# brd-relays3.net
KiCad netlist of a schematic drawn in EAGLE
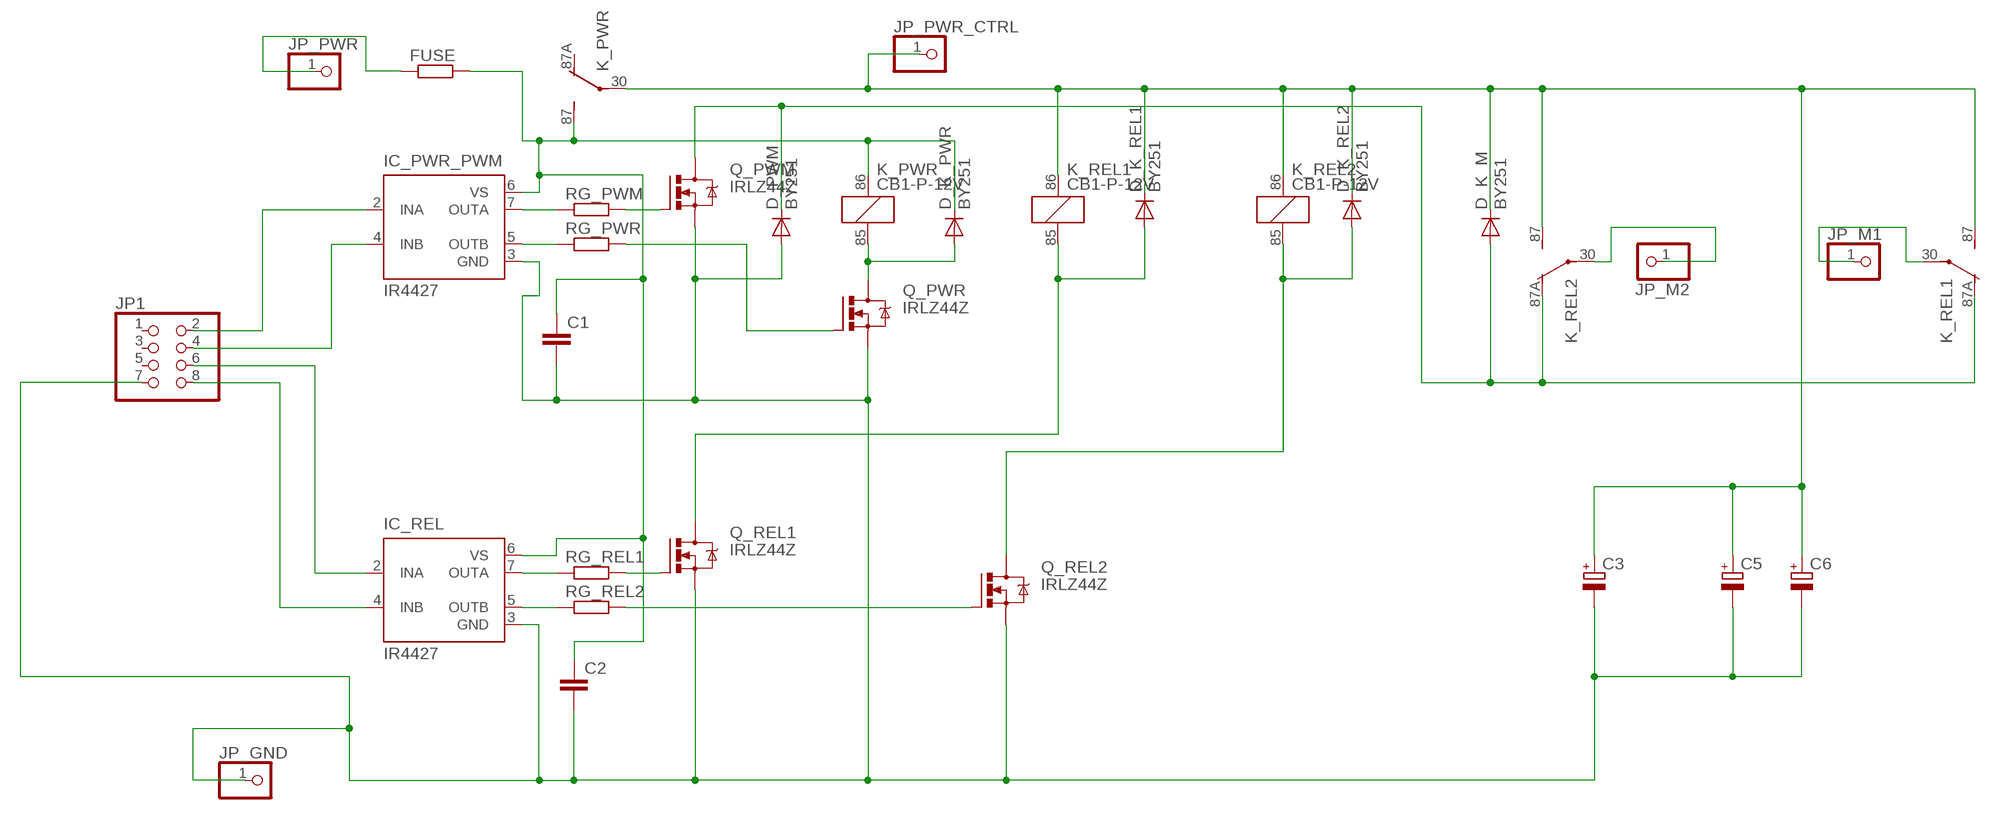
[diagram p0: schematic, sheet 1]

(export (version "E")
  (design (tool "Eeschema 10.0.6"))
  (components
    (comp (ref "C1")
      (value "C-EU050-055X075")
      (footprint "eagle-import:C050-055X075")
      (libsource (lib "eagle-import") (part "C-EU050-055X075"))
    )
    (comp (ref "C2")
      (value "C-EU050-055X075")
      (footprint "eagle-import:C050-055X075")
      (libsource (lib "eagle-import") (part "C-EU050-055X075"))
    )
    (comp (ref "C3")
      (value "CPOL-EUE5-13")
      (footprint "eagle-import:E5-13")
      (libsource (lib "eagle-import") (part "CPOL-EUE5-13"))
    )
    (comp (ref "C5")
      (value "CPOL-EUE5-13")
      (footprint "eagle-import:E5-13")
      (libsource (lib "eagle-import") (part "CPOL-EUE5-13"))
    )
    (comp (ref "C6")
      (value "CPOL-EUE5-13")
      (footprint "eagle-import:E5-13")
      (libsource (lib "eagle-import") (part "CPOL-EUE5-13"))
    )
    (comp (ref "D_K_M")
      (value "BY251")
      (footprint "eagle-import:DO201-15")
      (libsource (lib "eagle-import") (part "BY251"))
    )
    (comp (ref "D_K_PWR")
      (value "BY251")
      (footprint "eagle-import:DO201-15")
      (libsource (lib "eagle-import") (part "BY251"))
    )
    (comp (ref "D_K_REL1")
      (value "BY251")
      (footprint "eagle-import:DO201-15")
      (libsource (lib "eagle-import") (part "BY251"))
    )
    (comp (ref "D_K_REL2")
      (value "BY251")
      (footprint "eagle-import:DO201-15")
      (libsource (lib "eagle-import") (part "BY251"))
    )
    (comp (ref "D_PWM")
      (value "BY251")
      (footprint "eagle-import:DO201-15")
      (libsource (lib "eagle-import") (part "BY251"))
    )
    (comp (ref "FUSE")
      (value "R-EU_0207/10")
      (footprint "eagle-import:FUSE_PACK1")
      (libsource (lib "eagle-import") (part "R-EU_0207/10"))
    )
    (comp (ref "IC_PWR_PWM")
      (value "IR4427")
      (footprint "eagle-import:DIL08")
      (fields (field (name "MF") "INTERNATIONAL RECTIFIER(IR)"))
      (libsource (lib "eagle-import") (part "IR4427"))
    )
    (comp (ref "IC_REL")
      (value "IR4427")
      (footprint "eagle-import:DIL08")
      (fields (field (name "MF") "INTERNATIONAL RECTIFIER(IR)"))
      (libsource (lib "eagle-import") (part "IR4427"))
    )
    (comp (ref "JP1")
      (value "PINHD-2X4")
      (footprint "eagle-import:2X04")
      (libsource (lib "eagle-import") (part "PINHD-2X4"))
    )
    (comp (ref "JP_GND")
      (value "PINHD-1X1")
      (footprint "eagle-import:1X01")
      (libsource (lib "eagle-import") (part "PINHD-1X1"))
    )
    (comp (ref "JP_M1")
      (value "PINHD-1X1")
      (footprint "eagle-import:1X01")
      (libsource (lib "eagle-import") (part "PINHD-1X1"))
    )
    (comp (ref "JP_M2")
      (value "PINHD-1X1")
      (footprint "eagle-import:1X01")
      (libsource (lib "eagle-import") (part "PINHD-1X1"))
    )
    (comp (ref "JP_PWR")
      (value "PINHD-1X1")
      (footprint "eagle-import:1X01")
      (libsource (lib "eagle-import") (part "PINHD-1X1"))
    )
    (comp (ref "JP_PWR_CTRL")
      (value "PINHD-1X1")
      (footprint "eagle-import:1X01")
      (libsource (lib "eagle-import") (part "PINHD-1X1"))
    )
    (comp (ref "K_PWR")
      (value "CB1-P-12V")
      (footprint "eagle-import:CB1")
      (fields (field (name "MF") "AROMAT/ MATSUSHITA"))
      (libsource (lib "eagle-import") (part "CB1-P-12V"))
    )
    (comp (ref "K_REL1")
      (value "CB1-P-12V")
      (footprint "eagle-import:CB1")
      (fields (field (name "MF") "AROMAT/ MATSUSHITA"))
      (libsource (lib "eagle-import") (part "CB1-P-12V"))
    )
    (comp (ref "K_REL2")
      (value "CB1-P-12V")
      (footprint "eagle-import:CB1")
      (fields (field (name "MF") "AROMAT/ MATSUSHITA"))
      (libsource (lib "eagle-import") (part "CB1-P-12V"))
    )
    (comp (ref "Q_PWM")
      (value "IRLZ44Z")
      (footprint "eagle-import:TO220BH")
      (libsource (lib "eagle-import") (part "IRLZ44Z"))
    )
    (comp (ref "Q_PWR")
      (value "IRLZ44Z")
      (footprint "eagle-import:TO220BH")
      (libsource (lib "eagle-import") (part "IRLZ44Z"))
    )
    (comp (ref "Q_REL1")
      (value "IRLZ44Z")
      (footprint "eagle-import:TO220BH")
      (libsource (lib "eagle-import") (part "IRLZ44Z"))
    )
    (comp (ref "Q_REL2")
      (value "IRLZ44Z")
      (footprint "eagle-import:TO220BH")
      (libsource (lib "eagle-import") (part "IRLZ44Z"))
    )
    (comp (ref "RG_PWM")
      (value "R-EU_0207/10")
      (footprint "eagle-import:0207_10")
      (libsource (lib "eagle-import") (part "rcl_R-EU_0207/10"))
    )
    (comp (ref "RG_PWR")
      (value "R-EU_0207/10")
      (footprint "eagle-import:0207_10")
      (libsource (lib "eagle-import") (part "rcl_R-EU_0207/10"))
    )
    (comp (ref "RG_REL1")
      (value "R-EU_0207/10")
      (footprint "eagle-import:0207_10")
      (libsource (lib "eagle-import") (part "rcl_R-EU_0207/10"))
    )
    (comp (ref "RG_REL2")
      (value "R-EU_0207/10")
      (footprint "eagle-import:0207_10")
      (libsource (lib "eagle-import") (part "rcl_R-EU_0207/10"))
    )
  )
  (nets
    (net (code "1") (name "Net-(FUSE-Pad1)") (class "Default")
      (node (ref "FUSE") (pin "1") (pinfunction "1_1") (pintype "passive"))
      (node (ref "JP_PWR") (pin "1") (pinfunction "1_1") (pintype "passive"))
    )
    (net (code "2") (name "Net-(IC_PWR_PWM-GND)") (class "Default")
      (node (ref "C1") (pin "2") (pinfunction "2_2") (pintype "passive"))
      (node (ref "C2") (pin "2") (pinfunction "2_2") (pintype "passive"))
      (node (ref "C3") (pin "-") (pinfunction "-_-") (pintype "passive"))
      (node (ref "C5") (pin "-") (pinfunction "-_-") (pintype "passive"))
      (node (ref "C6") (pin "-") (pinfunction "-_-") (pintype "passive"))
      (node (ref "D_PWM") (pin "A") (pinfunction "A_A") (pintype "passive"))
      (node (ref "IC_PWR_PWM") (pin "3") (pinfunction "GND_3") (pintype "power_in"))
      (node (ref "IC_REL") (pin "3") (pinfunction "GND_3") (pintype "power_in"))
      (node (ref "JP1") (pin "7") (pinfunction "7_7") (pintype "passive"))
      (node (ref "JP_GND") (pin "1") (pinfunction "1_1") (pintype "passive"))
      (node (ref "Q_PWM") (pin "S") (pinfunction "S_S") (pintype "passive"))
      (node (ref "Q_PWR") (pin "S") (pinfunction "S_S") (pintype "passive"))
      (node (ref "Q_REL1") (pin "S") (pinfunction "S_S") (pintype "passive"))
      (node (ref "Q_REL2") (pin "S") (pinfunction "S_S") (pintype "passive"))
    )
    (net (code "3") (name "Net-(IC_PWR_PWM-INA)") (class "Default")
      (node (ref "IC_PWR_PWM") (pin "2") (pinfunction "INA_2") (pintype "input"))
      (node (ref "JP1") (pin "2") (pinfunction "2_2") (pintype "passive"))
    )
    (net (code "4") (name "Net-(IC_PWR_PWM-INB)") (class "Default")
      (node (ref "IC_PWR_PWM") (pin "4") (pinfunction "INB_4") (pintype "input"))
      (node (ref "JP1") (pin "4") (pinfunction "4_4") (pintype "passive"))
    )
    (net (code "5") (name "Net-(IC_PWR_PWM-OUTA)") (class "Default")
      (node (ref "IC_PWR_PWM") (pin "7") (pinfunction "OUTA_7") (pintype "output"))
      (node (ref "RG_PWM") (pin "1") (pinfunction "1_1") (pintype "passive"))
    )
    (net (code "6") (name "Net-(IC_PWR_PWM-OUTB)") (class "Default")
      (node (ref "IC_PWR_PWM") (pin "5") (pinfunction "OUTB_5") (pintype "output"))
      (node (ref "RG_PWR") (pin "1") (pinfunction "1_1") (pintype "passive"))
    )
    (net (code "7") (name "Net-(IC_PWR_PWM-VS)") (class "Default")
      (node (ref "C1") (pin "1") (pinfunction "1_1") (pintype "passive"))
      (node (ref "C2") (pin "1") (pinfunction "1_1") (pintype "passive"))
      (node (ref "D_K_PWR") (pin "C") (pinfunction "C_C") (pintype "passive"))
      (node (ref "FUSE") (pin "2") (pinfunction "2_2") (pintype "passive"))
      (node (ref "IC_PWR_PWM") (pin "6") (pinfunction "VS_6") (pintype "power_in"))
      (node (ref "IC_REL") (pin "6") (pinfunction "VS_6") (pintype "power_in"))
      (node (ref "K_PWR") (pin "86") (pinfunction "1_86") (pintype "passive"))
      (node (ref "K_PWR") (pin "87") (pinfunction "S_87") (pintype "passive"))
    )
    (net (code "8") (name "Net-(IC_REL-INA)") (class "Default")
      (node (ref "IC_REL") (pin "2") (pinfunction "INA_2") (pintype "input"))
      (node (ref "JP1") (pin "6") (pinfunction "6_6") (pintype "passive"))
    )
    (net (code "9") (name "Net-(IC_REL-INB)") (class "Default")
      (node (ref "IC_REL") (pin "4") (pinfunction "INB_4") (pintype "input"))
      (node (ref "JP1") (pin "8") (pinfunction "8_8") (pintype "passive"))
    )
    (net (code "10") (name "Net-(IC_REL-OUTA)") (class "Default")
      (node (ref "IC_REL") (pin "7") (pinfunction "OUTA_7") (pintype "output"))
      (node (ref "RG_REL1") (pin "1") (pinfunction "1_1") (pintype "passive"))
    )
    (net (code "11") (name "Net-(IC_REL-OUTB)") (class "Default")
      (node (ref "IC_REL") (pin "5") (pinfunction "OUTB_5") (pintype "output"))
      (node (ref "RG_REL2") (pin "1") (pinfunction "1_1") (pintype "passive"))
    )
    (net (code "12") (name "Net-(K_PWRA-2)") (class "Default")
      (node (ref "D_K_PWR") (pin "A") (pinfunction "A_A") (pintype "passive"))
      (node (ref "K_PWR") (pin "85") (pinfunction "2_85") (pintype "passive"))
      (node (ref "Q_PWR") (pin "D") (pinfunction "D_D") (pintype "passive"))
    )
    (net (code "13") (name "Net-(K_PWRB-P)") (class "Default")
      (node (ref "C3") (pin "+") (pinfunction "+_+") (pintype "passive"))
      (node (ref "C5") (pin "+") (pinfunction "+_+") (pintype "passive"))
      (node (ref "C6") (pin "+") (pinfunction "+_+") (pintype "passive"))
      (node (ref "D_K_M") (pin "C") (pinfunction "C_C") (pintype "passive"))
      (node (ref "D_K_REL1") (pin "C") (pinfunction "C_C") (pintype "passive"))
      (node (ref "D_K_REL2") (pin "C") (pinfunction "C_C") (pintype "passive"))
      (node (ref "JP_PWR_CTRL") (pin "1") (pinfunction "1_1") (pintype "passive"))
      (node (ref "K_PWR") (pin "30") (pinfunction "P_30") (pintype "passive"))
      (node (ref "K_REL1") (pin "86") (pinfunction "1_86") (pintype "passive"))
      (node (ref "K_REL1") (pin "87") (pinfunction "S_87") (pintype "passive"))
      (node (ref "K_REL2") (pin "86") (pinfunction "1_86") (pintype "passive"))
      (node (ref "K_REL2") (pin "87") (pinfunction "S_87") (pintype "passive"))
    )
    (net (code "14") (name "Net-(K_REL1A-2)") (class "Default")
      (node (ref "D_K_REL1") (pin "A") (pinfunction "A_A") (pintype "passive"))
      (node (ref "K_REL1") (pin "85") (pinfunction "2_85") (pintype "passive"))
      (node (ref "Q_REL1") (pin "D") (pinfunction "D_D") (pintype "passive"))
    )
    (net (code "15") (name "Net-(K_REL1B-O)") (class "Default")
      (node (ref "D_K_M") (pin "A") (pinfunction "A_A") (pintype "passive"))
      (node (ref "D_PWM") (pin "C") (pinfunction "C_C") (pintype "passive"))
      (node (ref "K_REL1") (pin "87A") (pinfunction "O_87A") (pintype "passive"))
      (node (ref "K_REL2") (pin "87A") (pinfunction "O_87A") (pintype "passive"))
      (node (ref "Q_PWM") (pin "D") (pinfunction "D_D") (pintype "passive"))
    )
    (net (code "16") (name "Net-(K_REL1B-P)") (class "Default")
      (node (ref "JP_M1") (pin "1") (pinfunction "1_1") (pintype "passive"))
      (node (ref "K_REL1") (pin "30") (pinfunction "P_30") (pintype "passive"))
    )
    (net (code "17") (name "Net-(K_REL2A-2)") (class "Default")
      (node (ref "D_K_REL2") (pin "A") (pinfunction "A_A") (pintype "passive"))
      (node (ref "K_REL2") (pin "85") (pinfunction "2_85") (pintype "passive"))
      (node (ref "Q_REL2") (pin "D") (pinfunction "D_D") (pintype "passive"))
    )
    (net (code "18") (name "Net-(K_REL2B-P)") (class "Default")
      (node (ref "JP_M2") (pin "1") (pinfunction "1_1") (pintype "passive"))
      (node (ref "K_REL2") (pin "30") (pinfunction "P_30") (pintype "passive"))
    )
    (net (code "19") (name "Net-(Q_PWM-PadG)") (class "Default")
      (node (ref "Q_PWM") (pin "G") (pinfunction "G_G") (pintype "passive"))
      (node (ref "RG_PWM") (pin "2") (pinfunction "2_2") (pintype "passive"))
    )
    (net (code "20") (name "Net-(Q_PWR-PadG)") (class "Default")
      (node (ref "Q_PWR") (pin "G") (pinfunction "G_G") (pintype "passive"))
      (node (ref "RG_PWR") (pin "2") (pinfunction "2_2") (pintype "passive"))
    )
    (net (code "21") (name "Net-(Q_REL1-PadG)") (class "Default")
      (node (ref "Q_REL1") (pin "G") (pinfunction "G_G") (pintype "passive"))
      (node (ref "RG_REL1") (pin "2") (pinfunction "2_2") (pintype "passive"))
    )
    (net (code "22") (name "Net-(Q_REL2-PadG)") (class "Default")
      (node (ref "Q_REL2") (pin "G") (pinfunction "G_G") (pintype "passive"))
      (node (ref "RG_REL2") (pin "2") (pinfunction "2_2") (pintype "passive"))
    )
    (net (code "23") (name "unconnected-(JP1-Pad1)") (class "Default")
      (node (ref "JP1") (pin "1") (pinfunction "1_1") (pintype "passive"))
    )
    (net (code "24") (name "unconnected-(JP1-Pad3)") (class "Default")
      (node (ref "JP1") (pin "3") (pinfunction "3_3") (pintype "passive"))
    )
    (net (code "25") (name "unconnected-(JP1-Pad5)") (class "Default")
      (node (ref "JP1") (pin "5") (pinfunction "5_5") (pintype "passive"))
    )
    (net (code "26") (name "unconnected-(K_PWRB-O-Pad87A)") (class "Default")
      (node (ref "K_PWR") (pin "87A") (pinfunction "O_87A") (pintype "passive"))
    )
  )
)
